# bluetooth_BM20_part.net
KiCad netlist of a schematic drawn in EAGLE
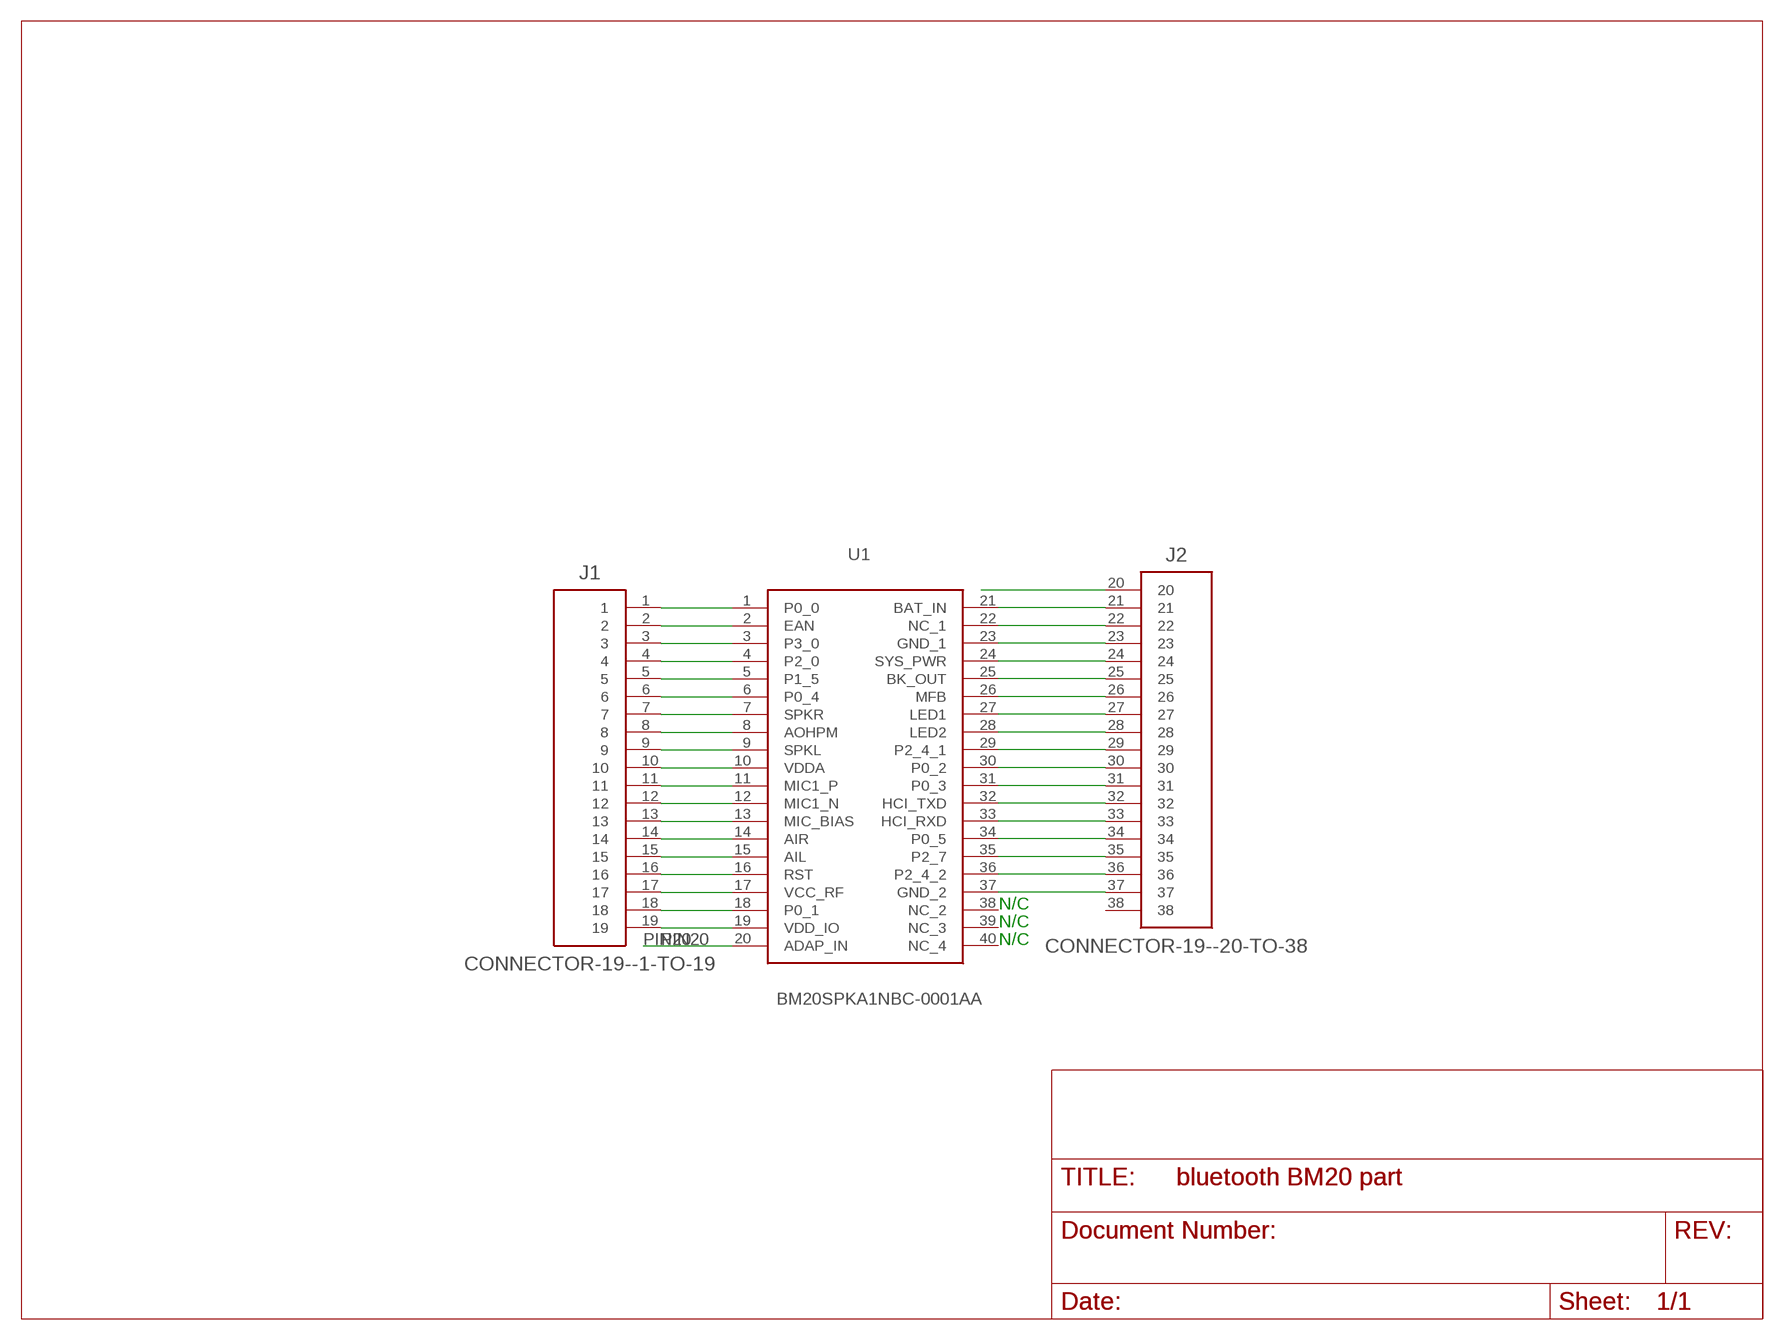
[diagram p0: schematic, sheet 1]

(export (version "E")
  (design (tool "Eeschema 10.0.6"))
  (components
    (comp (ref "J1")
      (value "CONNECTOR-19--1-TO-19")
      (footprint "eagle-import:ESQ-119-XX-XX-S")
      (libsource (lib "eagle-import") (part "CONNECTOR-19--1-TO-19"))
    )
    (comp (ref "J2")
      (value "CONNECTOR-19--20-TO-38")
      (footprint "eagle-import:ESQ-119-XX-XX-S--PIN-1-ROUND")
      (libsource (lib "eagle-import") (part "CONNECTOR-19--20-TO-38"))
    )
    (comp (ref "U1")
      (value "BM20SPKA1NBC-0001AA")
      (footprint "eagle-import:BM20SPKA1NBC0001AA")
      (fields (field (name "MOUSER_PART_NUMBER") "579-SPKA1NBC-0001AA"))
      (libsource (lib "eagle-import") (part "BM20SPKA1NBC-0001AA"))
    )
  )
  (nets
    (net (code "1") (name "/PIN20") (class "Default")
      (node (ref "J2") (pin "20") (pinfunction "20_20") (pintype "bidirectional"))
      (node (ref "U1") (pin "20") (pinfunction "ADAP_IN_20") (pintype "bidirectional"))
    )
    (net (code "2") (name "Net-(U1-AIL)") (class "Default")
      (node (ref "J1") (pin "15") (pinfunction "15_15") (pintype "bidirectional"))
      (node (ref "U1") (pin "15") (pinfunction "AIL_15") (pintype "bidirectional"))
    )
    (net (code "3") (name "Net-(U1-AIR)") (class "Default")
      (node (ref "J1") (pin "14") (pinfunction "14_14") (pintype "bidirectional"))
      (node (ref "U1") (pin "14") (pinfunction "AIR_14") (pintype "bidirectional"))
    )
    (net (code "4") (name "Net-(U1-AOHPM)") (class "Default")
      (node (ref "J1") (pin "8") (pinfunction "8_8") (pintype "bidirectional"))
      (node (ref "U1") (pin "8") (pinfunction "AOHPM_8") (pintype "bidirectional"))
    )
    (net (code "5") (name "Net-(U1-BAT_IN)") (class "Default")
      (node (ref "J2") (pin "21") (pinfunction "21_21") (pintype "bidirectional"))
      (node (ref "U1") (pin "21") (pinfunction "BAT_IN_21") (pintype "bidirectional"))
    )
    (net (code "6") (name "Net-(U1-BK_OUT)") (class "Default")
      (node (ref "J2") (pin "25") (pinfunction "25_25") (pintype "bidirectional"))
      (node (ref "U1") (pin "25") (pinfunction "BK_OUT_25") (pintype "bidirectional"))
    )
    (net (code "7") (name "Net-(U1-EAN)") (class "Default")
      (node (ref "J1") (pin "2") (pinfunction "2_2") (pintype "bidirectional"))
      (node (ref "U1") (pin "2") (pinfunction "EAN_2") (pintype "bidirectional"))
    )
    (net (code "8") (name "Net-(U1-GND_1)") (class "Default")
      (node (ref "J2") (pin "23") (pinfunction "23_23") (pintype "bidirectional"))
      (node (ref "U1") (pin "23") (pinfunction "GND_1_23") (pintype "bidirectional"))
    )
    (net (code "9") (name "Net-(U1-GND_2)") (class "Default")
      (node (ref "J2") (pin "37") (pinfunction "37_37") (pintype "bidirectional"))
      (node (ref "U1") (pin "37") (pinfunction "GND_2_37") (pintype "bidirectional"))
    )
    (net (code "10") (name "Net-(U1-HCI_RXD)") (class "Default")
      (node (ref "J2") (pin "33") (pinfunction "33_33") (pintype "bidirectional"))
      (node (ref "U1") (pin "33") (pinfunction "HCI_RXD_33") (pintype "bidirectional"))
    )
    (net (code "11") (name "Net-(U1-HCI_TXD)") (class "Default")
      (node (ref "J2") (pin "32") (pinfunction "32_32") (pintype "bidirectional"))
      (node (ref "U1") (pin "32") (pinfunction "HCI_TXD_32") (pintype "bidirectional"))
    )
    (net (code "12") (name "Net-(U1-LED1)") (class "Default")
      (node (ref "J2") (pin "27") (pinfunction "27_27") (pintype "bidirectional"))
      (node (ref "U1") (pin "27") (pinfunction "LED1_27") (pintype "bidirectional"))
    )
    (net (code "13") (name "Net-(U1-LED2)") (class "Default")
      (node (ref "J2") (pin "28") (pinfunction "28_28") (pintype "bidirectional"))
      (node (ref "U1") (pin "28") (pinfunction "LED2_28") (pintype "bidirectional"))
    )
    (net (code "14") (name "Net-(U1-MFB)") (class "Default")
      (node (ref "J2") (pin "26") (pinfunction "26_26") (pintype "bidirectional"))
      (node (ref "U1") (pin "26") (pinfunction "MFB_26") (pintype "bidirectional"))
    )
    (net (code "15") (name "Net-(U1-MIC1_N)") (class "Default")
      (node (ref "J1") (pin "12") (pinfunction "12_12") (pintype "bidirectional"))
      (node (ref "U1") (pin "12") (pinfunction "MIC1_N_12") (pintype "bidirectional"))
    )
    (net (code "16") (name "Net-(U1-MIC1_P)") (class "Default")
      (node (ref "J1") (pin "11") (pinfunction "11_11") (pintype "bidirectional"))
      (node (ref "U1") (pin "11") (pinfunction "MIC1_P_11") (pintype "bidirectional"))
    )
    (net (code "17") (name "Net-(U1-MIC_BIAS)") (class "Default")
      (node (ref "J1") (pin "13") (pinfunction "13_13") (pintype "bidirectional"))
      (node (ref "U1") (pin "13") (pinfunction "MIC_BIAS_13") (pintype "bidirectional"))
    )
    (net (code "18") (name "Net-(U1-NC_1)") (class "Default")
      (node (ref "J2") (pin "22") (pinfunction "22_22") (pintype "bidirectional"))
      (node (ref "U1") (pin "22") (pinfunction "NC_1_22") (pintype "bidirectional"))
    )
    (net (code "19") (name "Net-(U1-P0_0)") (class "Default")
      (node (ref "J1") (pin "1") (pinfunction "1_1") (pintype "bidirectional"))
      (node (ref "U1") (pin "1") (pinfunction "P0_0_1") (pintype "bidirectional"))
    )
    (net (code "20") (name "Net-(U1-P0_1)") (class "Default")
      (node (ref "J1") (pin "18") (pinfunction "18_18") (pintype "bidirectional"))
      (node (ref "U1") (pin "18") (pinfunction "P0_1_18") (pintype "bidirectional"))
    )
    (net (code "21") (name "Net-(U1-P0_2)") (class "Default")
      (node (ref "J2") (pin "30") (pinfunction "30_30") (pintype "bidirectional"))
      (node (ref "U1") (pin "30") (pinfunction "P0_2_30") (pintype "bidirectional"))
    )
    (net (code "22") (name "Net-(U1-P0_3)") (class "Default")
      (node (ref "J2") (pin "31") (pinfunction "31_31") (pintype "bidirectional"))
      (node (ref "U1") (pin "31") (pinfunction "P0_3_31") (pintype "bidirectional"))
    )
    (net (code "23") (name "Net-(U1-P0_4)") (class "Default")
      (node (ref "J1") (pin "6") (pinfunction "6_6") (pintype "bidirectional"))
      (node (ref "U1") (pin "6") (pinfunction "P0_4_6") (pintype "bidirectional"))
    )
    (net (code "24") (name "Net-(U1-P0_5)") (class "Default")
      (node (ref "J2") (pin "34") (pinfunction "34_34") (pintype "bidirectional"))
      (node (ref "U1") (pin "34") (pinfunction "P0_5_34") (pintype "bidirectional"))
    )
    (net (code "25") (name "Net-(U1-P1_5)") (class "Default")
      (node (ref "J1") (pin "5") (pinfunction "5_5") (pintype "bidirectional"))
      (node (ref "U1") (pin "5") (pinfunction "P1_5_5") (pintype "bidirectional"))
    )
    (net (code "26") (name "Net-(U1-P2_0)") (class "Default")
      (node (ref "J1") (pin "4") (pinfunction "4_4") (pintype "bidirectional"))
      (node (ref "U1") (pin "4") (pinfunction "P2_0_4") (pintype "bidirectional"))
    )
    (net (code "27") (name "Net-(U1-P2_4_1)") (class "Default")
      (node (ref "J2") (pin "29") (pinfunction "29_29") (pintype "bidirectional"))
      (node (ref "U1") (pin "29") (pinfunction "P2_4_1_29") (pintype "bidirectional"))
    )
    (net (code "28") (name "Net-(U1-P2_4_2)") (class "Default")
      (node (ref "J2") (pin "36") (pinfunction "36_36") (pintype "bidirectional"))
      (node (ref "U1") (pin "36") (pinfunction "P2_4_2_36") (pintype "bidirectional"))
    )
    (net (code "29") (name "Net-(U1-P2_7)") (class "Default")
      (node (ref "J2") (pin "35") (pinfunction "35_35") (pintype "bidirectional"))
      (node (ref "U1") (pin "35") (pinfunction "P2_7_35") (pintype "bidirectional"))
    )
    (net (code "30") (name "Net-(U1-P3_0)") (class "Default")
      (node (ref "J1") (pin "3") (pinfunction "3_3") (pintype "bidirectional"))
      (node (ref "U1") (pin "3") (pinfunction "P3_0_3") (pintype "bidirectional"))
    )
    (net (code "31") (name "Net-(U1-RST)") (class "Default")
      (node (ref "J1") (pin "16") (pinfunction "16_16") (pintype "bidirectional"))
      (node (ref "U1") (pin "16") (pinfunction "RST_16") (pintype "bidirectional"))
    )
    (net (code "32") (name "Net-(U1-SPKL)") (class "Default")
      (node (ref "J1") (pin "9") (pinfunction "9_9") (pintype "bidirectional"))
      (node (ref "U1") (pin "9") (pinfunction "SPKL_9") (pintype "bidirectional"))
    )
    (net (code "33") (name "Net-(U1-SPKR)") (class "Default")
      (node (ref "J1") (pin "7") (pinfunction "7_7") (pintype "bidirectional"))
      (node (ref "U1") (pin "7") (pinfunction "SPKR_7") (pintype "bidirectional"))
    )
    (net (code "34") (name "Net-(U1-SYS_PWR)") (class "Default")
      (node (ref "J2") (pin "24") (pinfunction "24_24") (pintype "bidirectional"))
      (node (ref "U1") (pin "24") (pinfunction "SYS_PWR_24") (pintype "bidirectional"))
    )
    (net (code "35") (name "Net-(U1-VCC_RF)") (class "Default")
      (node (ref "J1") (pin "17") (pinfunction "17_17") (pintype "bidirectional"))
      (node (ref "U1") (pin "17") (pinfunction "VCC_RF_17") (pintype "bidirectional"))
    )
    (net (code "36") (name "Net-(U1-VDDA)") (class "Default")
      (node (ref "J1") (pin "10") (pinfunction "10_10") (pintype "bidirectional"))
      (node (ref "U1") (pin "10") (pinfunction "VDDA_10") (pintype "bidirectional"))
    )
    (net (code "37") (name "Net-(U1-VDD_IO)") (class "Default")
      (node (ref "J1") (pin "19") (pinfunction "19_19") (pintype "bidirectional"))
      (node (ref "U1") (pin "19") (pinfunction "VDD_IO_19") (pintype "bidirectional"))
    )
    (net (code "38") (name "unconnected-(J2-Pad38)") (class "Default")
      (node (ref "J2") (pin "38") (pinfunction "38_38") (pintype "bidirectional"))
    )
    (net (code "39") (name "unconnected-(U1-NC_2-Pad38)") (class "Default")
      (node (ref "U1") (pin "38") (pinfunction "NC_2_38") (pintype "bidirectional"))
    )
    (net (code "40") (name "unconnected-(U1-NC_3-Pad39)") (class "Default")
      (node (ref "U1") (pin "39") (pinfunction "NC_3_39") (pintype "bidirectional"))
    )
    (net (code "41") (name "unconnected-(U1-NC_4-Pad40)") (class "Default")
      (node (ref "U1") (pin "40") (pinfunction "NC_4_40") (pintype "bidirectional"))
    )
  )
)
